# Dental_Support_V200.net
KiCad netlist of a schematic drawn in Altium Designer
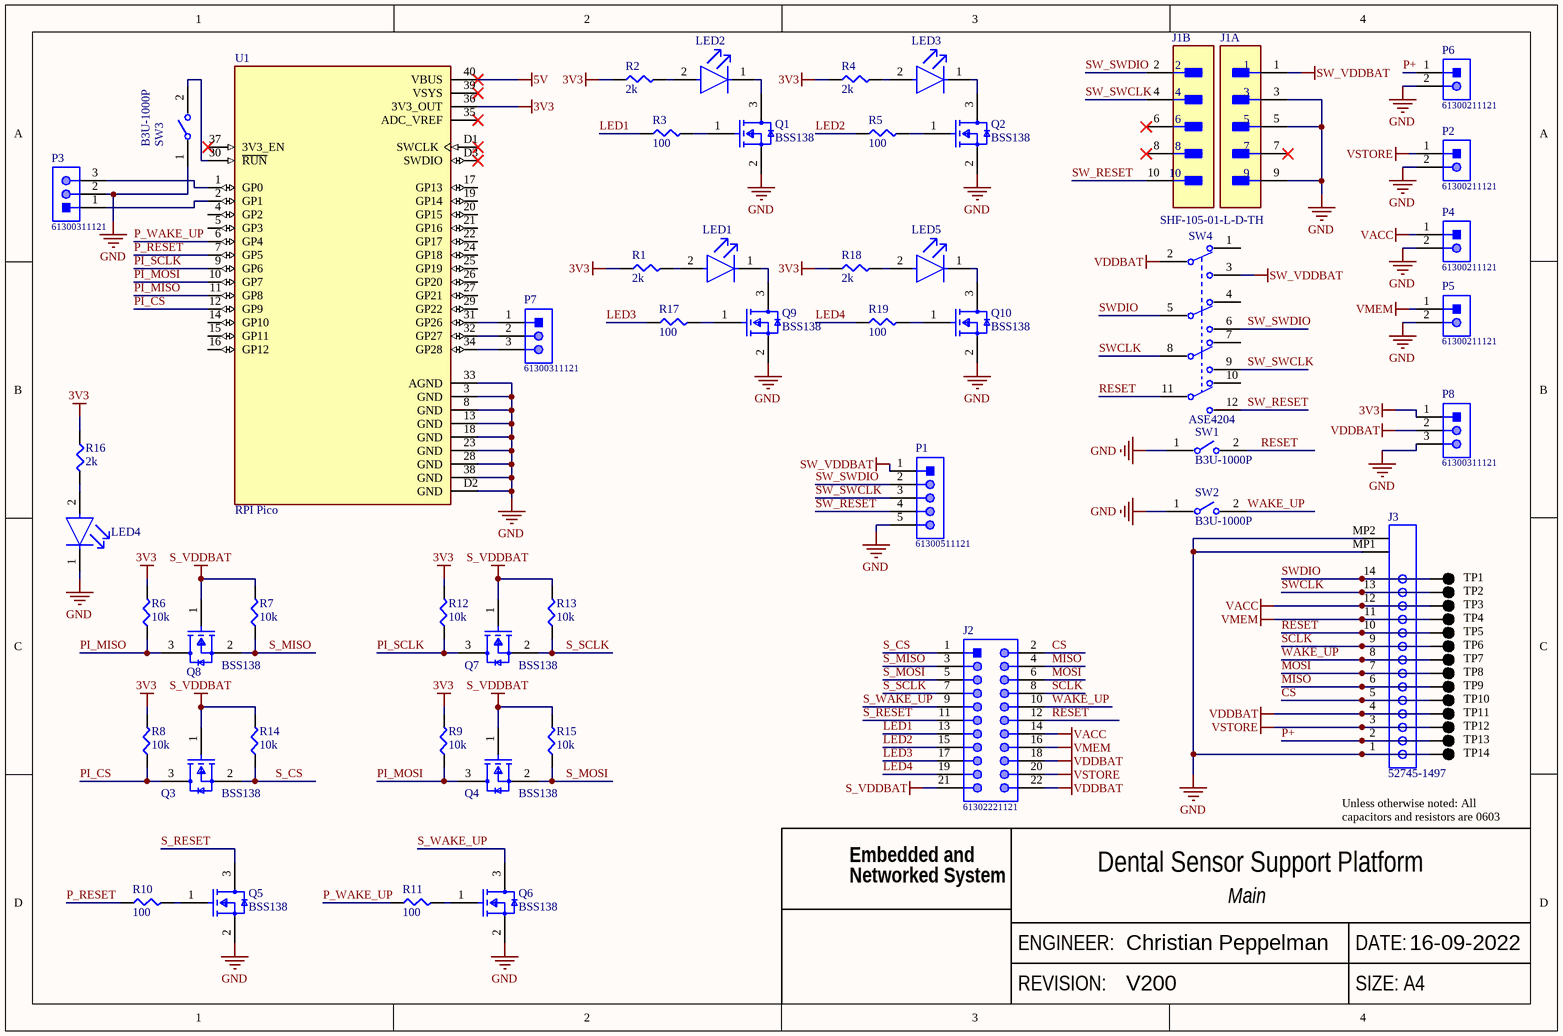
[diagram p0: Dental Support V200.SchDoc]

(export (version "E")
  (design (tool "Eeschema 10.0.6"))
  (components
    (comp (ref "J1")
      (value "SHF-105-01-L-D-TH")
      (footprint "FP-SHF-105-01-L-D-TH-MFG")
      (description "CONN HEADER VERT 10POS 1.27MM")
      (fields
        (field (name "MANUFACTURER") "Samtec")
        (field (name "OCTOPART") "https://octopart.com/shf-105-01-l-d-th-samtec-17904677")
      )
      (libsource (lib "Altium Content Vault") (part "544f42128f4185dcb88ce1ce9bf1982"))
    )
    (comp (ref "J2")
      (value "61302221121")
      (footprint "61302221121")
      (description "THT Vertical Pin Header WR-PHD, Pitch 2.54 mm, Dual Row, 22 pins")
      (fields (field (name "MANUFACTURER") "Wurth Elektronik") (field (name "PUBLISHER") "WurthElektronik"))
      (libsource (lib "Altium Content Vault") (part "WE-CN-2P-M-R22"))
    )
    (comp (ref "J3")
      (value "52745-1497")
      (footprint "MOLX-52745-1497")
      (fields (field (name "MANUFACTURER") "Molex"))
      (libsource (lib "Altium Content Vault") (part "MOLX-52745-1497"))
    )
    (comp (ref "LED1")
      (value "150080SS75000")
      (footprint "FP-150080SS75000-MFG")
      (description "LED RED CLEAR 0805 SMD")
      (libsource (lib "Altium Content Vault") (part "8706943c75ba83719d021d2fdc84c58"))
    )
    (comp (ref "LED2")
      (value "150080SS75000")
      (footprint "FP-150080SS75000-MFG")
      (description "LED RED CLEAR 0805 SMD")
      (libsource (lib "Altium Content Vault") (part "8706943c75ba83719d021d2fdc84c58"))
    )
    (comp (ref "LED3")
      (value "150080SS75000")
      (footprint "FP-150080SS75000-MFG")
      (description "LED RED CLEAR 0805 SMD")
      (libsource (lib "Altium Content Vault") (part "8706943c75ba83719d021d2fdc84c58"))
    )
    (comp (ref "LED4")
      (value "150080SS75000")
      (footprint "FP-150080SS75000-MFG")
      (description "LED RED CLEAR 0805 SMD")
      (libsource (lib "Altium Content Vault") (part "8706943c75ba83719d021d2fdc84c58"))
    )
    (comp (ref "LED5")
      (value "150080SS75000")
      (footprint "FP-150080SS75000-MFG")
      (description "LED RED CLEAR 0805 SMD")
      (libsource (lib "Altium Content Vault") (part "8706943c75ba83719d021d2fdc84c58"))
    )
    (comp (ref "P1")
      (value "61300511121")
      (footprint "61300511121")
      (description "THT Vertical Pin Header WR-PHD, Pitch 2.54 mm, Single Row, 5 pins")
      (fields (field (name "MANUFACTURER") "Wurth Elektronik") (field (name "PUBLISHER") "WurthElektronik"))
      (libsource (lib "Altium Content Vault") (part "WE-CN-1P-M-R5"))
    )
    (comp (ref "P2")
      (value "61300211121")
      (footprint "61300211121")
      (description "THT Vertical Pin Header WR-PHD, Pitch 2.54 mm, Single Row, 2 pins")
      (fields (field (name "MANUFACTURER") "Wurth Elektronik") (field (name "PUBLISHER") "WurthElektronik"))
      (libsource (lib "Altium Content Vault") (part "WE-CN-1P-M-R2"))
    )
    (comp (ref "P3")
      (value "61300311121")
      (footprint "61300311121")
      (description "THT Vertical Pin Header WR-PHD, Pitch 2.54 mm, Single Row, 3 pins")
      (fields (field (name "MANUFACTURER") "Wurth Elektronik") (field (name "PUBLISHER") "WurthElektronik"))
      (libsource (lib "") (part "WE-CN-1P-M-R3_1"))
    )
    (comp (ref "P4")
      (value "61300211121")
      (footprint "61300211121")
      (description "THT Vertical Pin Header WR-PHD, Pitch 2.54 mm, Single Row, 2 pins")
      (fields (field (name "MANUFACTURER") "Wurth Elektronik") (field (name "PUBLISHER") "WurthElektronik"))
      (libsource (lib "Altium Content Vault") (part "WE-CN-1P-M-R2"))
    )
    (comp (ref "P5")
      (value "61300211121")
      (footprint "61300211121")
      (description "THT Vertical Pin Header WR-PHD, Pitch 2.54 mm, Single Row, 2 pins")
      (fields (field (name "MANUFACTURER") "Wurth Elektronik") (field (name "PUBLISHER") "WurthElektronik"))
      (libsource (lib "Altium Content Vault") (part "WE-CN-1P-M-R2"))
    )
    (comp (ref "P6")
      (value "61300211121")
      (footprint "61300211121")
      (description "THT Vertical Pin Header WR-PHD, Pitch 2.54 mm, Single Row, 2 pins")
      (fields (field (name "MANUFACTURER") "Wurth Elektronik") (field (name "PUBLISHER") "WurthElektronik"))
      (libsource (lib "Altium Content Vault") (part "WE-CN-1P-M-R2"))
    )
    (comp (ref "P7")
      (value "61300311121")
      (footprint "61300311121")
      (description "THT Vertical Pin Header WR-PHD, Pitch 2.54 mm, Single Row, 3 pins")
      (fields (field (name "MANUFACTURER") "Wurth Elektronik") (field (name "PUBLISHER") "WurthElektronik"))
      (libsource (lib "Altium Content Vault") (part "WE-CN-1P-M-R3"))
    )
    (comp (ref "P8")
      (value "61300311121")
      (footprint "61300311121")
      (description "THT Vertical Pin Header WR-PHD, Pitch 2.54 mm, Single Row, 3 pins")
      (fields (field (name "MANUFACTURER") "Wurth Elektronik") (field (name "PUBLISHER") "WurthElektronik"))
      (libsource (lib "Altium Content Vault") (part "WE-CN-1P-M-R3"))
    )
    (comp (ref "Q1")
      (value "BSS138")
      (footprint "FP-318-08-IPC_B")
      (description "MOSFET N-CH 50V 220MA SOT-23")
      (libsource (lib "Altium Content Vault") (part "3b9c635fedb024a5347a57b145af9cc"))
    )
    (comp (ref "Q2")
      (value "BSS138")
      (footprint "FP-318-08-IPC_B")
      (description "MOSFET N-CH 50V 220MA SOT-23")
      (libsource (lib "Altium Content Vault") (part "3b9c635fedb024a5347a57b145af9cc"))
    )
    (comp (ref "Q3")
      (value "BSS138")
      (footprint "FP-318-08-IPC_B")
      (description "MOSFET N-CH 50V 220MA SOT-23")
      (libsource (lib "Altium Content Vault") (part "3b9c635fedb024a5347a57b145af9cc"))
    )
    (comp (ref "Q4")
      (value "BSS138")
      (footprint "FP-318-08-IPC_B")
      (description "MOSFET N-CH 50V 220MA SOT-23")
      (libsource (lib "Altium Content Vault") (part "3b9c635fedb024a5347a57b145af9cc"))
    )
    (comp (ref "Q5")
      (value "BSS138")
      (footprint "FP-318-08-IPC_B")
      (description "MOSFET N-CH 50V 220MA SOT-23")
      (libsource (lib "Altium Content Vault") (part "3b9c635fedb024a5347a57b145af9cc"))
    )
    (comp (ref "Q6")
      (value "BSS138")
      (footprint "FP-318-08-IPC_B")
      (description "MOSFET N-CH 50V 220MA SOT-23")
      (libsource (lib "Altium Content Vault") (part "3b9c635fedb024a5347a57b145af9cc"))
    )
    (comp (ref "Q7")
      (value "BSS138")
      (footprint "FP-318-08-IPC_B")
      (description "MOSFET N-CH 50V 220MA SOT-23")
      (libsource (lib "Altium Content Vault") (part "3b9c635fedb024a5347a57b145af9cc"))
    )
    (comp (ref "Q8")
      (value "BSS138")
      (footprint "FP-318-08-IPC_B")
      (description "MOSFET N-CH 50V 220MA SOT-23")
      (libsource (lib "Altium Content Vault") (part "3b9c635fedb024a5347a57b145af9cc"))
    )
    (comp (ref "Q9")
      (value "BSS138")
      (footprint "FP-318-08-IPC_B")
      (description "MOSFET N-CH 50V 220MA SOT-23")
      (libsource (lib "Altium Content Vault") (part "3b9c635fedb024a5347a57b145af9cc"))
    )
    (comp (ref "Q10")
      (value "BSS138")
      (footprint "FP-318-08-IPC_B")
      (description "MOSFET N-CH 50V 220MA SOT-23")
      (libsource (lib "Altium Content Vault") (part "3b9c635fedb024a5347a57b145af9cc"))
    )
    (comp (ref "R1")
      (value "2k")
      (footprint "RESC2012X06N")
      (description "RES SMD 2K OHM 1% 1/8W 0805")
      (fields
        (field (name "PART NUMBER") "ERJ-6ENF2001V")
        (field (name "DIGI-KEY PART NUMBER") "P2.00KCCT-ND")
      )
      (libsource (lib "Panasonic_ERJ_0805") (part "ERJ-6ENF2001V"))
    )
    (comp (ref "R2")
      (value "2k")
      (footprint "RESC2012X06N")
      (description "RES SMD 2K OHM 1% 1/8W 0805")
      (fields
        (field (name "PART NUMBER") "ERJ-6ENF2001V")
        (field (name "DIGI-KEY PART NUMBER") "P2.00KCCT-ND")
      )
      (libsource (lib "Panasonic_ERJ_0805") (part "ERJ-6ENF2001V"))
    )
    (comp (ref "R3")
      (value "100")
      (footprint "RESC2012X06N")
      (description "RES SMD 100 OHM 1% 1/8W 0805")
      (fields (field (name "PART NUMBER") "ERJ-6ENF1000V") (field (name "DIGI-KEY PART NUMBER") "P100CCT-ND"))
      (libsource (lib "Panasonic_ERJ_0805") (part "ERJ-6ENF1000V"))
    )
    (comp (ref "R4")
      (value "2k")
      (footprint "RESC2012X06N")
      (description "RES SMD 2K OHM 1% 1/8W 0805")
      (fields
        (field (name "PART NUMBER") "ERJ-6ENF2001V")
        (field (name "DIGI-KEY PART NUMBER") "P2.00KCCT-ND")
      )
      (libsource (lib "Panasonic_ERJ_0805") (part "ERJ-6ENF2001V"))
    )
    (comp (ref "R5")
      (value "100")
      (footprint "RESC2012X06N")
      (description "RES SMD 100 OHM 1% 1/8W 0805")
      (fields (field (name "PART NUMBER") "ERJ-6ENF1000V") (field (name "DIGI-KEY PART NUMBER") "P100CCT-ND"))
      (libsource (lib "Panasonic_ERJ_0805") (part "ERJ-6ENF1000V"))
    )
    (comp (ref "R6")
      (value "10k")
      (footprint "RESC2012X06N")
      (description "RES SMD 10K OHM 1% 1/8W 0805")
      (fields
        (field (name "PART NUMBER") "ERJ-6ENF1002V")
        (field (name "DIGI-KEY PART NUMBER") "P10.0KCCT-ND")
      )
      (libsource (lib "Panasonic_ERJ_0805") (part "ERJ-6ENF1002V"))
    )
    (comp (ref "R7")
      (value "10k")
      (footprint "RESC2012X06N")
      (description "RES SMD 10K OHM 1% 1/8W 0805")
      (fields
        (field (name "PART NUMBER") "ERJ-6ENF1002V")
        (field (name "DIGI-KEY PART NUMBER") "P10.0KCCT-ND")
      )
      (libsource (lib "Panasonic_ERJ_0805") (part "ERJ-6ENF1002V"))
    )
    (comp (ref "R8")
      (value "10k")
      (footprint "RESC2012X06N")
      (description "RES SMD 10K OHM 1% 1/8W 0805")
      (fields
        (field (name "PART NUMBER") "ERJ-6ENF1002V")
        (field (name "DIGI-KEY PART NUMBER") "P10.0KCCT-ND")
      )
      (libsource (lib "Panasonic_ERJ_0805") (part "ERJ-6ENF1002V"))
    )
    (comp (ref "R9")
      (value "10k")
      (footprint "RESC2012X06N")
      (description "RES SMD 10K OHM 1% 1/8W 0805")
      (fields
        (field (name "PART NUMBER") "ERJ-6ENF1002V")
        (field (name "DIGI-KEY PART NUMBER") "P10.0KCCT-ND")
      )
      (libsource (lib "Panasonic_ERJ_0805") (part "ERJ-6ENF1002V"))
    )
    (comp (ref "R10")
      (value "100")
      (footprint "RESC2012X06N")
      (description "RES SMD 100 OHM 1% 1/8W 0805")
      (fields (field (name "PART NUMBER") "ERJ-6ENF1000V") (field (name "DIGI-KEY PART NUMBER") "P100CCT-ND"))
      (libsource (lib "Panasonic_ERJ_0805") (part "ERJ-6ENF1000V"))
    )
    (comp (ref "R11")
      (value "100")
      (footprint "RESC2012X06N")
      (description "RES SMD 100 OHM 1% 1/8W 0805")
      (fields (field (name "PART NUMBER") "ERJ-6ENF1000V") (field (name "DIGI-KEY PART NUMBER") "P100CCT-ND"))
      (libsource (lib "Panasonic_ERJ_0805") (part "ERJ-6ENF1000V"))
    )
    (comp (ref "R12")
      (value "10k")
      (footprint "RESC2012X06N")
      (description "RES SMD 10K OHM 1% 1/8W 0805")
      (fields
        (field (name "PART NUMBER") "ERJ-6ENF1002V")
        (field (name "DIGI-KEY PART NUMBER") "P10.0KCCT-ND")
      )
      (libsource (lib "Panasonic_ERJ_0805") (part "ERJ-6ENF1002V"))
    )
    (comp (ref "R13")
      (value "10k")
      (footprint "RESC2012X06N")
      (description "RES SMD 10K OHM 1% 1/8W 0805")
      (fields
        (field (name "PART NUMBER") "ERJ-6ENF1002V")
        (field (name "DIGI-KEY PART NUMBER") "P10.0KCCT-ND")
      )
      (libsource (lib "Panasonic_ERJ_0805") (part "ERJ-6ENF1002V"))
    )
    (comp (ref "R14")
      (value "10k")
      (footprint "RESC2012X06N")
      (description "RES SMD 10K OHM 1% 1/8W 0805")
      (fields
        (field (name "PART NUMBER") "ERJ-6ENF1002V")
        (field (name "DIGI-KEY PART NUMBER") "P10.0KCCT-ND")
      )
      (libsource (lib "Panasonic_ERJ_0805") (part "ERJ-6ENF1002V"))
    )
    (comp (ref "R15")
      (value "10k")
      (footprint "RESC2012X06N")
      (description "RES SMD 10K OHM 1% 1/8W 0805")
      (fields
        (field (name "PART NUMBER") "ERJ-6ENF1002V")
        (field (name "DIGI-KEY PART NUMBER") "P10.0KCCT-ND")
      )
      (libsource (lib "Panasonic_ERJ_0805") (part "ERJ-6ENF1002V"))
    )
    (comp (ref "R16")
      (value "2k")
      (footprint "RESC2012X06N")
      (description "RES SMD 2K OHM 1% 1/8W 0805")
      (fields
        (field (name "PART NUMBER") "ERJ-6ENF2001V")
        (field (name "DIGI-KEY PART NUMBER") "P2.00KCCT-ND")
      )
      (libsource (lib "Panasonic_ERJ_0805") (part "ERJ-6ENF2001V"))
    )
    (comp (ref "R17")
      (value "100")
      (footprint "RESC2012X06N")
      (description "RES SMD 100 OHM 1% 1/8W 0805")
      (fields (field (name "PART NUMBER") "ERJ-6ENF1000V") (field (name "DIGI-KEY PART NUMBER") "P100CCT-ND"))
      (libsource (lib "Panasonic_ERJ_0805") (part "ERJ-6ENF1000V"))
    )
    (comp (ref "R18")
      (value "2k")
      (footprint "RESC2012X06N")
      (description "RES SMD 2K OHM 1% 1/8W 0805")
      (fields
        (field (name "PART NUMBER") "ERJ-6ENF2001V")
        (field (name "DIGI-KEY PART NUMBER") "P2.00KCCT-ND")
      )
      (libsource (lib "Panasonic_ERJ_0805") (part "ERJ-6ENF2001V"))
    )
    (comp (ref "R19")
      (value "100")
      (footprint "RESC2012X06N")
      (description "RES SMD 100 OHM 1% 1/8W 0805")
      (fields (field (name "PART NUMBER") "ERJ-6ENF1000V") (field (name "DIGI-KEY PART NUMBER") "P100CCT-ND"))
      (libsource (lib "Panasonic_ERJ_0805") (part "ERJ-6ENF1000V"))
    )
    (comp (ref "SW1")
      (value "B3U-1000P")
      (footprint "FP-B3U-1000P-MFG")
      (description "SWITCH TACTILE SPST-NO 0.05A 12V")
      (libsource (lib "Altium Content Vault") (part "ae622034201233ca1abcedc05908f33"))
    )
    (comp (ref "SW2")
      (value "B3U-1000P")
      (footprint "FP-B3U-1000P-MFG")
      (description "SWITCH TACTILE SPST-NO 0.05A 12V")
      (libsource (lib "Altium Content Vault") (part "ae622034201233ca1abcedc05908f33"))
    )
    (comp (ref "SW3")
      (value "B3U-1000P")
      (footprint "FP-B3U-1000P-MFG")
      (description "SWITCH TACTILE SPST-NO 0.05A 12V")
      (libsource (lib "Altium Content Vault") (part "ae622034201233ca1abcedc05908f33"))
    )
    (comp (ref "SW4")
      (value "ASE4204")
      (footprint "FP-ASE4204-MFG")
      (description "Pushbutton Switch SPST-NO Keyswitch, Illuminated Through Hole")
      (libsource (lib "Altium Content Vault") (part "ed2fb4c80255b159646d1d6e4c6c74d"))
    )
    (comp (ref "TP1")
      (value "5011")
      (footprint "KSTN-5011_V")
      (description "Test Point, Black, Through Hole, RoHS, Bulk")
      (fields (field (name "MANUFACTURER") "Keystone"))
      (libsource (lib "Altium Content Vault") (part "TESTPOINT_BLACK"))
    )
    (comp (ref "TP2")
      (value "5011")
      (footprint "KSTN-5011_V")
      (description "Test Point, Black, Through Hole, RoHS, Bulk")
      (fields (field (name "MANUFACTURER") "Keystone"))
      (libsource (lib "Altium Content Vault") (part "TESTPOINT_BLACK"))
    )
    (comp (ref "TP3")
      (value "5011")
      (footprint "KSTN-5011_V")
      (description "Test Point, Black, Through Hole, RoHS, Bulk")
      (fields (field (name "MANUFACTURER") "Keystone"))
      (libsource (lib "Altium Content Vault") (part "TESTPOINT_BLACK"))
    )
    (comp (ref "TP4")
      (value "5011")
      (footprint "KSTN-5011_V")
      (description "Test Point, Black, Through Hole, RoHS, Bulk")
      (fields (field (name "MANUFACTURER") "Keystone"))
      (libsource (lib "Altium Content Vault") (part "TESTPOINT_BLACK"))
    )
    (comp (ref "TP5")
      (value "5011")
      (footprint "KSTN-5011_V")
      (description "Test Point, Black, Through Hole, RoHS, Bulk")
      (fields (field (name "MANUFACTURER") "Keystone"))
      (libsource (lib "Altium Content Vault") (part "TESTPOINT_BLACK"))
    )
    (comp (ref "TP6")
      (value "5011")
      (footprint "KSTN-5011_V")
      (description "Test Point, Black, Through Hole, RoHS, Bulk")
      (fields (field (name "MANUFACTURER") "Keystone"))
      (libsource (lib "Altium Content Vault") (part "TESTPOINT_BLACK"))
    )
    (comp (ref "TP7")
      (value "5011")
      (footprint "KSTN-5011_V")
      (description "Test Point, Black, Through Hole, RoHS, Bulk")
      (fields (field (name "MANUFACTURER") "Keystone"))
      (libsource (lib "Altium Content Vault") (part "TESTPOINT_BLACK"))
    )
    (comp (ref "TP8")
      (value "5011")
      (footprint "KSTN-5011_V")
      (description "Test Point, Black, Through Hole, RoHS, Bulk")
      (fields (field (name "MANUFACTURER") "Keystone"))
      (libsource (lib "Altium Content Vault") (part "TESTPOINT_BLACK"))
    )
    (comp (ref "TP9")
      (value "5011")
      (footprint "KSTN-5011_V")
      (description "Test Point, Black, Through Hole, RoHS, Bulk")
      (fields (field (name "MANUFACTURER") "Keystone"))
      (libsource (lib "Altium Content Vault") (part "TESTPOINT_BLACK"))
    )
    (comp (ref "TP10")
      (value "5011")
      (footprint "KSTN-5011_V")
      (description "Test Point, Black, Through Hole, RoHS, Bulk")
      (fields (field (name "MANUFACTURER") "Keystone"))
      (libsource (lib "Altium Content Vault") (part "TESTPOINT_BLACK"))
    )
    (comp (ref "TP11")
      (value "5011")
      (footprint "KSTN-5011_V")
      (description "Test Point, Black, Through Hole, RoHS, Bulk")
      (fields (field (name "MANUFACTURER") "Keystone"))
      (libsource (lib "Altium Content Vault") (part "TESTPOINT_BLACK"))
    )
    (comp (ref "TP12")
      (value "5011")
      (footprint "KSTN-5011_V")
      (description "Test Point, Black, Through Hole, RoHS, Bulk")
      (fields (field (name "MANUFACTURER") "Keystone"))
      (libsource (lib "Altium Content Vault") (part "TESTPOINT_BLACK"))
    )
    (comp (ref "TP13")
      (value "5011")
      (footprint "KSTN-5011_V")
      (description "Test Point, Black, Through Hole, RoHS, Bulk")
      (fields (field (name "MANUFACTURER") "Keystone"))
      (libsource (lib "Altium Content Vault") (part "TESTPOINT_BLACK"))
    )
    (comp (ref "TP14")
      (value "5011")
      (footprint "KSTN-5011_V")
      (description "Test Point, Black, Through Hole, RoHS, Bulk")
      (fields (field (name "MANUFACTURER") "Keystone"))
      (libsource (lib "Altium Content Vault") (part "TESTPOINT_BLACK"))
    )
    (comp (ref "U1") (value "RPI Pico") (footprint "RPI Pico") (libsource (lib "Library") (part "RPI Pico")))
  )
  (nets
    (net (code "1") (name "/CS") (class "Default")
      (node (ref "J2") (pin "2") (pinfunction "2_2") (pintype "passive"))
      (node (ref "J3") (pin "5") (pinfunction "5_5") (pintype "passive"))
      (node (ref "TP10") (pin "1") (pinfunction "1_1") (pintype "passive"))
    )
    (net (code "2") (name "/LED1") (class "Default")
      (node (ref "J2") (pin "13") (pinfunction "13_13") (pintype "passive"))
      (node (ref "R3") (pin "1") (pinfunction "1_1") (pintype "passive"))
    )
    (net (code "3") (name "/LED2") (class "Default")
      (node (ref "J2") (pin "15") (pinfunction "15_15") (pintype "passive"))
      (node (ref "R5") (pin "1") (pinfunction "1_1") (pintype "passive"))
    )
    (net (code "4") (name "/LED3") (class "Default")
      (node (ref "J2") (pin "17") (pinfunction "17_17") (pintype "passive"))
      (node (ref "R17") (pin "1") (pinfunction "1_1") (pintype "passive"))
    )
    (net (code "5") (name "/LED4") (class "Default")
      (node (ref "J2") (pin "19") (pinfunction "19_19") (pintype "passive"))
      (node (ref "R19") (pin "1") (pinfunction "1_1") (pintype "passive"))
    )
    (net (code "6") (name "/MISO") (class "Default")
      (node (ref "J2") (pin "4") (pinfunction "4_4") (pintype "passive"))
      (node (ref "J3") (pin "6") (pinfunction "6_6") (pintype "passive"))
      (node (ref "TP9") (pin "1") (pinfunction "1_1") (pintype "passive"))
    )
    (net (code "7") (name "/MOSI") (class "Default")
      (node (ref "J2") (pin "6") (pinfunction "6_6") (pintype "passive"))
      (node (ref "J3") (pin "7") (pinfunction "7_7") (pintype "passive"))
      (node (ref "TP8") (pin "1") (pinfunction "1_1") (pintype "passive"))
    )
    (net (code "8") (name "/P+") (class "Default")
      (node (ref "J3") (pin "2") (pinfunction "2_2") (pintype "passive"))
      (node (ref "P6") (pin "1") (pinfunction "1_1") (pintype "passive"))
      (node (ref "TP13") (pin "1") (pinfunction "1_1") (pintype "passive"))
    )
    (net (code "9") (name "/PI_CS") (class "Default")
      (node (ref "Q3") (pin "3") (pinfunction "D_3") (pintype "passive"))
      (node (ref "R8") (pin "1") (pinfunction "1_1") (pintype "passive"))
      (node (ref "U1") (pin "12") (pinfunction "GP9_12") (pintype "bidirectional"))
    )
    (net (code "10") (name "/PI_MISO") (class "Default")
      (node (ref "Q8") (pin "3") (pinfunction "D_3") (pintype "passive"))
      (node (ref "R6") (pin "1") (pinfunction "1_1") (pintype "passive"))
      (node (ref "U1") (pin "11") (pinfunction "GP8_11") (pintype "bidirectional"))
    )
    (net (code "11") (name "/PI_MOSI") (class "Default")
      (node (ref "Q4") (pin "3") (pinfunction "D_3") (pintype "passive"))
      (node (ref "R9") (pin "1") (pinfunction "1_1") (pintype "passive"))
      (node (ref "U1") (pin "10") (pinfunction "GP7_10") (pintype "bidirectional"))
    )
    (net (code "12") (name "/PI_SCLK") (class "Default")
      (node (ref "Q7") (pin "3") (pinfunction "D_3") (pintype "passive"))
      (node (ref "R12") (pin "1") (pinfunction "1_1") (pintype "passive"))
      (node (ref "U1") (pin "9") (pinfunction "GP6_9") (pintype "bidirectional"))
    )
    (net (code "13") (name "/P_RESET") (class "Default")
      (node (ref "R10") (pin "1") (pinfunction "1_1") (pintype "passive"))
      (node (ref "U1") (pin "7") (pinfunction "GP5_7") (pintype "bidirectional"))
    )
    (net (code "14") (name "/P_WAKE_UP") (class "Default")
      (node (ref "R11") (pin "1") (pinfunction "1_1") (pintype "passive"))
      (node (ref "U1") (pin "6") (pinfunction "GP4_6") (pintype "bidirectional"))
    )
    (net (code "15") (name "/RESET") (class "Default")
      (node (ref "J2") (pin "12") (pinfunction "12_12") (pintype "passive"))
      (node (ref "J3") (pin "10") (pinfunction "10_10") (pintype "passive"))
      (node (ref "SW1") (pin "2") (pinfunction "2_2") (pintype "passive"))
      (node (ref "SW4") (pin "11") (pinfunction "11_11") (pintype "passive"))
      (node (ref "TP5") (pin "1") (pinfunction "1_1") (pintype "passive"))
    )
    (net (code "16") (name "/SCLK") (class "Default")
      (node (ref "J2") (pin "8") (pinfunction "8_8") (pintype "passive"))
      (node (ref "J3") (pin "9") (pinfunction "9_9") (pintype "passive"))
      (node (ref "TP6") (pin "1") (pinfunction "1_1") (pintype "passive"))
    )
    (net (code "17") (name "/SWCLK") (class "Default")
      (node (ref "J3") (pin "13") (pinfunction "13_13") (pintype "passive"))
      (node (ref "SW4") (pin "8") (pinfunction "8_8") (pintype "passive"))
      (node (ref "TP2") (pin "1") (pinfunction "1_1") (pintype "passive"))
    )
    (net (code "18") (name "/SWDIO") (class "Default")
      (node (ref "J3") (pin "14") (pinfunction "14_14") (pintype "passive"))
      (node (ref "SW4") (pin "5") (pinfunction "5_5") (pintype "passive"))
      (node (ref "TP1") (pin "1") (pinfunction "1_1") (pintype "passive"))
    )
    (net (code "19") (name "/SW_RESET") (class "Default")
      (node (ref "J1") (pin "10") (pinfunction "10_10") (pintype "passive"))
      (node (ref "P1") (pin "4") (pinfunction "4_4") (pintype "passive"))
      (node (ref "SW4") (pin "12") (pinfunction "12_12") (pintype "passive"))
    )
    (net (code "20") (name "/SW_SWCLK") (class "Default")
      (node (ref "J1") (pin "4") (pinfunction "4_4") (pintype "passive"))
      (node (ref "P1") (pin "3") (pinfunction "3_3") (pintype "passive"))
      (node (ref "SW4") (pin "9") (pinfunction "9_9") (pintype "passive"))
    )
    (net (code "21") (name "/SW_SWDIO") (class "Default")
      (node (ref "J1") (pin "2") (pinfunction "2_2") (pintype "passive"))
      (node (ref "P1") (pin "2") (pinfunction "2_2") (pintype "passive"))
      (node (ref "SW4") (pin "6") (pinfunction "6_6") (pintype "passive"))
    )
    (net (code "22") (name "/S_CS") (class "Default")
      (node (ref "J2") (pin "1") (pinfunction "1_1") (pintype "passive"))
      (node (ref "Q3") (pin "2") (pinfunction "S_2") (pintype "passive"))
      (node (ref "R14") (pin "1") (pinfunction "1_1") (pintype "passive"))
    )
    (net (code "23") (name "/S_MISO") (class "Default")
      (node (ref "J2") (pin "3") (pinfunction "3_3") (pintype "passive"))
      (node (ref "Q8") (pin "2") (pinfunction "S_2") (pintype "passive"))
      (node (ref "R7") (pin "1") (pinfunction "1_1") (pintype "passive"))
    )
    (net (code "24") (name "/S_MOSI") (class "Default")
      (node (ref "J2") (pin "5") (pinfunction "5_5") (pintype "passive"))
      (node (ref "Q4") (pin "2") (pinfunction "S_2") (pintype "passive"))
      (node (ref "R15") (pin "1") (pinfunction "1_1") (pintype "passive"))
    )
    (net (code "25") (name "/S_RESET") (class "Default")
      (node (ref "J2") (pin "11") (pinfunction "11_11") (pintype "passive"))
      (node (ref "Q5") (pin "3") (pinfunction "D_3") (pintype "passive"))
    )
    (net (code "26") (name "/S_SCLK") (class "Default")
      (node (ref "J2") (pin "7") (pinfunction "7_7") (pintype "passive"))
      (node (ref "Q7") (pin "2") (pinfunction "S_2") (pintype "passive"))
      (node (ref "R13") (pin "1") (pinfunction "1_1") (pintype "passive"))
    )
    (net (code "27") (name "/S_WAKE_UP") (class "Default")
      (node (ref "J2") (pin "9") (pinfunction "9_9") (pintype "passive"))
      (node (ref "Q6") (pin "3") (pinfunction "D_3") (pintype "passive"))
    )
    (net (code "28") (name "/WAKE_UP") (class "Default")
      (node (ref "J2") (pin "10") (pinfunction "10_10") (pintype "passive"))
      (node (ref "J3") (pin "8") (pinfunction "8_8") (pintype "passive"))
      (node (ref "SW2") (pin "2") (pinfunction "2_2") (pintype "passive"))
      (node (ref "TP7") (pin "1") (pinfunction "1_1") (pintype "passive"))
    )
    (net (code "29") (name "3V3") (class "Default")
      (node (ref "P8") (pin "1") (pinfunction "1_1") (pintype "passive"))
      (node (ref "R1") (pin "1") (pinfunction "1_1") (pintype "passive"))
      (node (ref "R12") (pin "2") (pinfunction "2_2") (pintype "passive"))
      (node (ref "R16") (pin "1") (pinfunction "1_1") (pintype "passive"))
      (node (ref "R18") (pin "1") (pinfunction "1_1") (pintype "passive"))
      (node (ref "R2") (pin "1") (pinfunction "1_1") (pintype "passive"))
      (node (ref "R4") (pin "1") (pinfunction "1_1") (pintype "passive"))
      (node (ref "R6") (pin "2") (pinfunction "2_2") (pintype "passive"))
      (node (ref "R8") (pin "2") (pinfunction "2_2") (pintype "passive"))
      (node (ref "R9") (pin "2") (pinfunction "2_2") (pintype "passive"))
      (node (ref "U1") (pin "36") (pinfunction "3V3_OUT_36") (pintype "power_in"))
    )
    (net (code "30") (name "5V") (class "Default")
      (node (ref "U1") (pin "40") (pinfunction "VBUS_40") (pintype "power_in"))
    )
    (net (code "31") (name "GND") (class "Default")
      (node (ref "J1") (pin "3") (pinfunction "3_3") (pintype "passive"))
      (node (ref "J1") (pin "5") (pinfunction "5_5") (pintype "passive"))
      (node (ref "J1") (pin "9") (pinfunction "9_9") (pintype "passive"))
      (node (ref "J3") (pin "1") (pinfunction "1_1") (pintype "passive"))
      (node (ref "J3") (pin "MP1") (pinfunction "MP1_MP1") (pintype "passive"))
      (node (ref "J3") (pin "MP2") (pinfunction "MP2_MP2") (pintype "passive"))
      (node (ref "LED4") (pin "1") (pinfunction "C_1") (pintype "passive"))
      (node (ref "P1") (pin "5") (pinfunction "5_5") (pintype "passive"))
      (node (ref "P2") (pin "2") (pinfunction "2_2") (pintype "passive"))
      (node (ref "P3") (pin "2") (pinfunction "2_2") (pintype "passive"))
      (node (ref "P4") (pin "2") (pinfunction "2_2") (pintype "passive"))
      (node (ref "P5") (pin "2") (pinfunction "2_2") (pintype "passive"))
      (node (ref "P6") (pin "2") (pinfunction "2_2") (pintype "passive"))
      (node (ref "P8") (pin "3") (pinfunction "3_3") (pintype "passive"))
      (node (ref "Q1") (pin "2") (pinfunction "S_2") (pintype "passive"))
      (node (ref "Q10") (pin "2") (pinfunction "S_2") (pintype "passive"))
      (node (ref "Q2") (pin "2") (pinfunction "S_2") (pintype "passive"))
      (node (ref "Q5") (pin "2") (pinfunction "S_2") (pintype "passive"))
      (node (ref "Q6") (pin "2") (pinfunction "S_2") (pintype "passive"))
      (node (ref "Q9") (pin "2") (pinfunction "S_2") (pintype "passive"))
      (node (ref "SW1") (pin "1") (pinfunction "1_1") (pintype "passive"))
      (node (ref "SW2") (pin "1") (pinfunction "1_1") (pintype "passive"))
      (node (ref "SW3") (pin "1") (pinfunction "1_1") (pintype "passive"))
      (node (ref "TP14") (pin "1") (pinfunction "1_1") (pintype "passive"))
      (node (ref "U1") (pin "13") (pinfunction "GND_13") (pintype "power_in"))
      (node (ref "U1") (pin "18") (pinfunction "GND_18") (pintype "power_in"))
      (node (ref "U1") (pin "23") (pinfunction "GND_23") (pintype "power_in"))
      (node (ref "U1") (pin "28") (pinfunction "GND_28") (pintype "power_in"))
      (node (ref "U1") (pin "3") (pinfunction "GND_3") (pintype "power_in"))
      (node (ref "U1") (pin "33") (pinfunction "AGND_33") (pintype "power_in"))
      (node (ref "U1") (pin "38") (pinfunction "GND_38") (pintype "power_in"))
      (node (ref "U1") (pin "8") (pinfunction "GND_8") (pintype "power_in"))
      (node (ref "U1") (pin "D2") (pinfunction "GND_D2") (pintype "power_in"))
    )
    (net (code "32") (name "Net-(LED1-A)") (class "Default")
      (node (ref "LED1") (pin "2") (pinfunction "A_2") (pintype "passive"))
      (node (ref "R1") (pin "2") (pinfunction "2_2") (pintype "passive"))
    )
    (net (code "33") (name "Net-(LED1-C)") (class "Default")
      (node (ref "LED1") (pin "1") (pinfunction "C_1") (pintype "passive"))
      (node (ref "Q9") (pin "3") (pinfunction "D_3") (pintype "passive"))
    )
    (net (code "34") (name "Net-(LED2-A)") (class "Default")
      (node (ref "LED2") (pin "2") (pinfunction "A_2") (pintype "passive"))
      (node (ref "R2") (pin "2") (pinfunction "2_2") (pintype "passive"))
    )
    (net (code "35") (name "Net-(LED2-C)") (class "Default")
      (node (ref "LED2") (pin "1") (pinfunction "C_1") (pintype "passive"))
      (node (ref "Q1") (pin "3") (pinfunction "D_3") (pintype "passive"))
    )
    (net (code "36") (name "Net-(LED3-A)") (class "Default")
      (node (ref "LED3") (pin "2") (pinfunction "A_2") (pintype "passive"))
      (node (ref "R4") (pin "2") (pinfunction "2_2") (pintype "passive"))
    )
    (net (code "37") (name "Net-(LED3-C)") (class "Default")
      (node (ref "LED3") (pin "1") (pinfunction "C_1") (pintype "passive"))
      (node (ref "Q2") (pin "3") (pinfunction "D_3") (pintype "passive"))
    )
    (net (code "38") (name "Net-(LED4-A)") (class "Default")
      (node (ref "LED4") (pin "2") (pinfunction "A_2") (pintype "passive"))
      (node (ref "R16") (pin "2") (pinfunction "2_2") (pintype "passive"))
    )
    (net (code "39") (name "Net-(LED5-A)") (class "Default")
      (node (ref "LED5") (pin "2") (pinfunction "A_2") (pintype "passive"))
      (node (ref "R18") (pin "2") (pinfunction "2_2") (pintype "passive"))
    )
    (net (code "40") (name "Net-(LED5-C)") (class "Default")
      (node (ref "LED5") (pin "1") (pinfunction "C_1") (pintype "passive"))
      (node (ref "Q10") (pin "3") (pinfunction "D_3") (pintype "passive"))
    )
    (net (code "41") (name "Net-(Q1-G)") (class "Default")
      (node (ref "Q1") (pin "1") (pinfunction "G_1") (pintype "passive"))
      (node (ref "R3") (pin "2") (pinfunction "2_2") (pintype "passive"))
    )
    (net (code "42") (name "Net-(Q2-G)") (class "Default")
      (node (ref "Q2") (pin "1") (pinfunction "G_1") (pintype "passive"))
      (node (ref "R5") (pin "2") (pinfunction "2_2") (pintype "passive"))
    )
    (net (code "43") (name "Net-(Q5-G)") (class "Default")
      (node (ref "Q5") (pin "1") (pinfunction "G_1") (pintype "passive"))
      (node (ref "R10") (pin "2") (pinfunction "2_2") (pintype "passive"))
    )
    (net (code "44") (name "Net-(Q6-G)") (class "Default")
      (node (ref "Q6") (pin "1") (pinfunction "G_1") (pintype "passive"))
      (node (ref "R11") (pin "2") (pinfunction "2_2") (pintype "passive"))
    )
    (net (code "45") (name "Net-(Q9-G)") (class "Default")
      (node (ref "Q9") (pin "1") (pinfunction "G_1") (pintype "passive"))
      (node (ref "R17") (pin "2") (pinfunction "2_2") (pintype "passive"))
    )
    (net (code "46") (name "Net-(Q10-G)") (class "Default")
      (node (ref "Q10") (pin "1") (pinfunction "G_1") (pintype "passive"))
      (node (ref "R19") (pin "2") (pinfunction "2_2") (pintype "passive"))
    )
    (net (code "47") (name "Net-(U1-GP0)") (class "Default")
      (node (ref "P3") (pin "3") (pinfunction "3_3") (pintype "passive"))
      (node (ref "U1") (pin "1") (pinfunction "GP0_1") (pintype "bidirectional"))
    )
    (net (code "48") (name "Net-(U1-GP1)") (class "Default")
      (node (ref "P3") (pin "1") (pinfunction "1_1") (pintype "passive"))
      (node (ref "U1") (pin "2") (pinfunction "GP1_2") (pintype "bidirectional"))
    )
    (net (code "49") (name "Net-(U1-GP26)") (class "Default")
      (node (ref "P7") (pin "1") (pinfunction "1_1") (pintype "passive"))
      (node (ref "U1") (pin "31") (pinfunction "GP26_31") (pintype "bidirectional"))
    )
    (net (code "50") (name "Net-(U1-GP27)") (class "Default")
      (node (ref "P7") (pin "2") (pinfunction "2_2") (pintype "passive"))
      (node (ref "U1") (pin "32") (pinfunction "GP27_32") (pintype "bidirectional"))
    )
    (net (code "51") (name "Net-(U1-GP28)") (class "Default")
      (node (ref "P7") (pin "3") (pinfunction "3_3") (pintype "passive"))
      (node (ref "U1") (pin "34") (pinfunction "GP28_34") (pintype "bidirectional"))
    )
    (net (code "52") (name "Net-(U1-~{RUN})") (class "Default")
      (node (ref "SW3") (pin "2") (pinfunction "2_2") (pintype "passive"))
      (node (ref "U1") (pin "30") (pinfunction "~{RUN}_30") (pintype "input"))
    )
    (net (code "53") (name "SW_VDDBAT") (class "Default")
      (node (ref "J1") (pin "1") (pinfunction "1_1") (pintype "passive"))
      (node (ref "P1") (pin "1") (pinfunction "1_1") (pintype "passive"))
      (node (ref "SW4") (pin "3") (pinfunction "3_3") (pintype "passive"))
    )
    (net (code "54") (name "S_VDDBAT") (class "Default")
      (node (ref "J2") (pin "21") (pinfunction "21_21") (pintype "passive"))
      (node (ref "Q3") (pin "1") (pinfunction "G_1") (pintype "passive"))
      (node (ref "Q4") (pin "1") (pinfunction "G_1") (pintype "passive"))
      (node (ref "Q7") (pin "1") (pinfunction "G_1") (pintype "passive"))
      (node (ref "Q8") (pin "1") (pinfunction "G_1") (pintype "passive"))
      (node (ref "R13") (pin "2") (pinfunction "2_2") (pintype "passive"))
      (node (ref "R14") (pin "2") (pinfunction "2_2") (pintype "passive"))
      (node (ref "R15") (pin "2") (pinfunction "2_2") (pintype "passive"))
      (node (ref "R7") (pin "2") (pinfunction "2_2") (pintype "passive"))
    )
    (net (code "55") (name "VACC") (class "Default")
      (node (ref "J2") (pin "14") (pinfunction "14_14") (pintype "passive"))
      (node (ref "J3") (pin "12") (pinfunction "12_12") (pintype "passive"))
      (node (ref "P4") (pin "1") (pinfunction "1_1") (pintype "passive"))
      (node (ref "TP3") (pin "1") (pinfunction "1_1") (pintype "passive"))
    )
    (net (code "56") (name "VDDBAT") (class "Default")
      (node (ref "J2") (pin "18") (pinfunction "18_18") (pintype "passive"))
      (node (ref "J2") (pin "22") (pinfunction "22_22") (pintype "passive"))
      (node (ref "J3") (pin "4") (pinfunction "4_4") (pintype "passive"))
      (node (ref "P8") (pin "2") (pinfunction "2_2") (pintype "passive"))
      (node (ref "SW4") (pin "2") (pinfunction "2_2") (pintype "passive"))
      (node (ref "TP11") (pin "1") (pinfunction "1_1") (pintype "passive"))
    )
    (net (code "57") (name "VMEM") (class "Default")
      (node (ref "J2") (pin "16") (pinfunction "16_16") (pintype "passive"))
      (node (ref "J3") (pin "11") (pinfunction "11_11") (pintype "passive"))
      (node (ref "P5") (pin "1") (pinfunction "1_1") (pintype "passive"))
      (node (ref "TP4") (pin "1") (pinfunction "1_1") (pintype "passive"))
    )
    (net (code "58") (name "VSTORE") (class "Default")
      (node (ref "J2") (pin "20") (pinfunction "20_20") (pintype "passive"))
      (node (ref "J3") (pin "3") (pinfunction "3_3") (pintype "passive"))
      (node (ref "P2") (pin "1") (pinfunction "1_1") (pintype "passive"))
      (node (ref "TP12") (pin "1") (pinfunction "1_1") (pintype "passive"))
    )
    (net (code "59") (name "unconnected-(J1-Pad6)") (class "Default")
      (node (ref "J1") (pin "6") (pinfunction "6_6") (pintype "passive+no_connect"))
    )
    (net (code "60") (name "unconnected-(J1-Pad7)") (class "Default")
      (node (ref "J1") (pin "7") (pinfunction "7_7") (pintype "passive+no_connect"))
    )
    (net (code "61") (name "unconnected-(J1-Pad8)") (class "Default")
      (node (ref "J1") (pin "8") (pinfunction "8_8") (pintype "passive+no_connect"))
    )
    (net (code "62") (name "unconnected-(SW4-Pad1)") (class "Default")
      (node (ref "SW4") (pin "1") (pinfunction "1_1") (pintype "passive"))
    )
    (net (code "63") (name "unconnected-(SW4-Pad4)") (class "Default")
      (node (ref "SW4") (pin "4") (pinfunction "4_4") (pintype "passive"))
    )
    (net (code "64") (name "unconnected-(SW4-Pad7)") (class "Default")
      (node (ref "SW4") (pin "7") (pinfunction "7_7") (pintype "passive"))
    )
    (net (code "65") (name "unconnected-(SW4-Pad10)") (class "Default")
      (node (ref "SW4") (pin "10") (pinfunction "10_10") (pintype "passive"))
    )
    (net (code "66") (name "unconnected-(U1-3V3_EN-Pad37)") (class "Default")
      (node (ref "U1") (pin "37") (pinfunction "3V3_EN_37") (pintype "input+no_connect"))
    )
    (net (code "67") (name "unconnected-(U1-ADC_VREF-Pad35)") (class "Default")
      (node (ref "U1") (pin "35") (pinfunction "ADC_VREF_35") (pintype "power_in+no_connect"))
    )
    (net (code "68") (name "unconnected-(U1-GP2-Pad4)") (class "Default")
      (node (ref "U1") (pin "4") (pinfunction "GP2_4") (pintype "bidirectional"))
    )
    (net (code "69") (name "unconnected-(U1-GP3-Pad5)") (class "Default")
      (node (ref "U1") (pin "5") (pinfunction "GP3_5") (pintype "bidirectional"))
    )
    (net (code "70") (name "unconnected-(U1-GP10-Pad14)") (class "Default")
      (node (ref "U1") (pin "14") (pinfunction "GP10_14") (pintype "bidirectional"))
    )
    (net (code "71") (name "unconnected-(U1-GP11-Pad15)") (class "Default")
      (node (ref "U1") (pin "15") (pinfunction "GP11_15") (pintype "bidirectional"))
    )
    (net (code "72") (name "unconnected-(U1-GP12-Pad16)") (class "Default")
      (node (ref "U1") (pin "16") (pinfunction "GP12_16") (pintype "bidirectional"))
    )
    (net (code "73") (name "unconnected-(U1-GP13-Pad17)") (class "Default")
      (node (ref "U1") (pin "17") (pinfunction "GP13_17") (pintype "bidirectional"))
    )
    (net (code "74") (name "unconnected-(U1-GP14-Pad19)") (class "Default")
      (node (ref "U1") (pin "19") (pinfunction "GP14_19") (pintype "bidirectional"))
    )
    (net (code "75") (name "unconnected-(U1-GP15-Pad20)") (class "Default")
      (node (ref "U1") (pin "20") (pinfunction "GP15_20") (pintype "bidirectional"))
    )
    (net (code "76") (name "unconnected-(U1-GP16-Pad21)") (class "Default")
      (node (ref "U1") (pin "21") (pinfunction "GP16_21") (pintype "bidirectional"))
    )
    (net (code "77") (name "unconnected-(U1-GP17-Pad22)") (class "Default")
      (node (ref "U1") (pin "22") (pinfunction "GP17_22") (pintype "bidirectional"))
    )
    (net (code "78") (name "unconnected-(U1-GP18-Pad24)") (class "Default")
      (node (ref "U1") (pin "24") (pinfunction "GP18_24") (pintype "bidirectional"))
    )
    (net (code "79") (name "unconnected-(U1-GP19-Pad25)") (class "Default")
      (node (ref "U1") (pin "25") (pinfunction "GP19_25") (pintype "bidirectional"))
    )
    (net (code "80") (name "unconnected-(U1-GP20-Pad26)") (class "Default")
      (node (ref "U1") (pin "26") (pinfunction "GP20_26") (pintype "bidirectional"))
    )
    (net (code "81") (name "unconnected-(U1-GP21-Pad27)") (class "Default")
      (node (ref "U1") (pin "27") (pinfunction "GP21_27") (pintype "bidirectional"))
    )
    (net (code "82") (name "unconnected-(U1-GP22-Pad29)") (class "Default")
      (node (ref "U1") (pin "29") (pinfunction "GP22_29") (pintype "bidirectional"))
    )
    (net (code "83") (name "unconnected-(U1-SWCLK-PadD1)") (class "Default")
      (node (ref "U1") (pin "D1") (pinfunction "SWCLK_D1") (pintype "input+no_connect"))
    )
    (net (code "84") (name "unconnected-(U1-SWDIO-PadD3)") (class "Default")
      (node (ref "U1") (pin "D3") (pinfunction "SWDIO_D3") (pintype "bidirectional+no_connect"))
    )
    (net (code "85") (name "unconnected-(U1-VSYS-Pad39)") (class "Default")
      (node (ref "U1") (pin "39") (pinfunction "VSYS_39") (pintype "power_in+no_connect"))
    )
  )
)
